# NEOPIXELS.net
KiCad netlist of a schematic drawn in Altium Designer
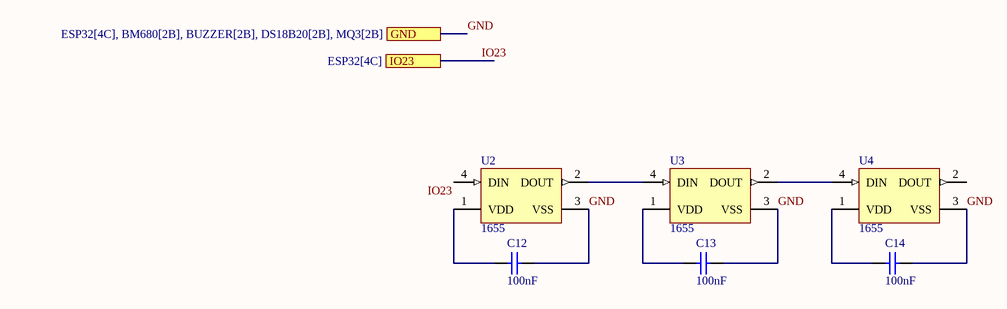
[diagram p0: NEOPIXELS.SchDoc]

(export (version "E")
  (design (tool "Eeschema 10.0.6"))
  (components
    (comp (ref "C12")
      (value "100nF")
      (footprint "CAPC2013X140X50ML20T25")
      (description "10µF ±10% 16V Ceramic Capacitor X5R 0805 (2012 Metric)")
      (fields (field (name "PART NUMBER") "CL21A106KOQNNNG"))
      (libsource (lib "Altium Content Vault") (part "CAP"))
    )
    (comp (ref "C13")
      (value "100nF")
      (footprint "CAPC2013X140X50ML20T25")
      (description "10µF ±10% 16V Ceramic Capacitor X5R 0805 (2012 Metric)")
      (fields (field (name "PART NUMBER") "CL21A106KOQNNNG"))
      (libsource (lib "Altium Content Vault") (part "CAP"))
    )
    (comp (ref "C14")
      (value "100nF")
      (footprint "CAPC2013X140X50ML20T25")
      (description "10µF ±10% 16V Ceramic Capacitor X5R 0805 (2012 Metric)")
      (fields (field (name "PART NUMBER") "CL21A106KOQNNNG"))
      (libsource (lib "Altium Content Vault") (part "CAP"))
    )
    (comp (ref "U2")
      (value "1655")
      (footprint "ADA-RGB-1655_V")
      (fields (field (name "MANUFACTURER") "Adafruit-Industries-LLC"))
      (libsource (lib "Altium Content Vault") (part "ADA-RGB-1655-4"))
    )
    (comp (ref "U3")
      (value "1655")
      (footprint "ADA-RGB-1655_V")
      (fields (field (name "MANUFACTURER") "Adafruit-Industries-LLC"))
      (libsource (lib "Altium Content Vault") (part "ADA-RGB-1655-4"))
    )
    (comp (ref "U4")
      (value "1655")
      (footprint "ADA-RGB-1655_V")
      (fields (field (name "MANUFACTURER") "Adafruit-Industries-LLC"))
      (libsource (lib "Altium Content Vault") (part "ADA-RGB-1655-4"))
    )
  )
  (nets
    (net (code "1") (name "/GND") (class "Default")
      (node (ref "C12") (pin "1") (pinfunction "1_1") (pintype "passive"))
      (node (ref "C13") (pin "1") (pinfunction "1_1") (pintype "passive"))
      (node (ref "C14") (pin "1") (pinfunction "1_1") (pintype "passive"))
      (node (ref "U2") (pin "3") (pinfunction "VSS_3") (pintype "power_in"))
      (node (ref "U3") (pin "3") (pinfunction "VSS_3") (pintype "power_in"))
      (node (ref "U4") (pin "3") (pinfunction "VSS_3") (pintype "power_in"))
    )
    (net (code "2") (name "/IO23") (class "Default")
      (node (ref "U2") (pin "4") (pinfunction "DIN_4") (pintype "input"))
    )
    (net (code "3") (name "Net-(U2-DOUT)") (class "Default")
      (node (ref "U2") (pin "2") (pinfunction "DOUT_2") (pintype "output"))
      (node (ref "U3") (pin "4") (pinfunction "DIN_4") (pintype "input"))
    )
    (net (code "4") (name "Net-(U2-VDD)") (class "Default")
      (node (ref "C12") (pin "2") (pinfunction "2_2") (pintype "passive"))
      (node (ref "U2") (pin "1") (pinfunction "VDD_1") (pintype "power_in"))
    )
    (net (code "5") (name "Net-(U3-DOUT)") (class "Default")
      (node (ref "U3") (pin "2") (pinfunction "DOUT_2") (pintype "output"))
      (node (ref "U4") (pin "4") (pinfunction "DIN_4") (pintype "input"))
    )
    (net (code "6") (name "Net-(U3-VDD)") (class "Default")
      (node (ref "C13") (pin "2") (pinfunction "2_2") (pintype "passive"))
      (node (ref "U3") (pin "1") (pinfunction "VDD_1") (pintype "power_in"))
    )
    (net (code "7") (name "Net-(U4-VDD)") (class "Default")
      (node (ref "C14") (pin "2") (pinfunction "2_2") (pintype "passive"))
      (node (ref "U4") (pin "1") (pinfunction "VDD_1") (pintype "power_in"))
    )
    (net (code "8") (name "unconnected-(U4-DOUT-Pad2)") (class "Default")
      (node (ref "U4") (pin "2") (pinfunction "DOUT_2") (pintype "output"))
    )
  )
)
